# Radar_Analog.net
KiCad netlist of a schematic drawn in Altium Designer
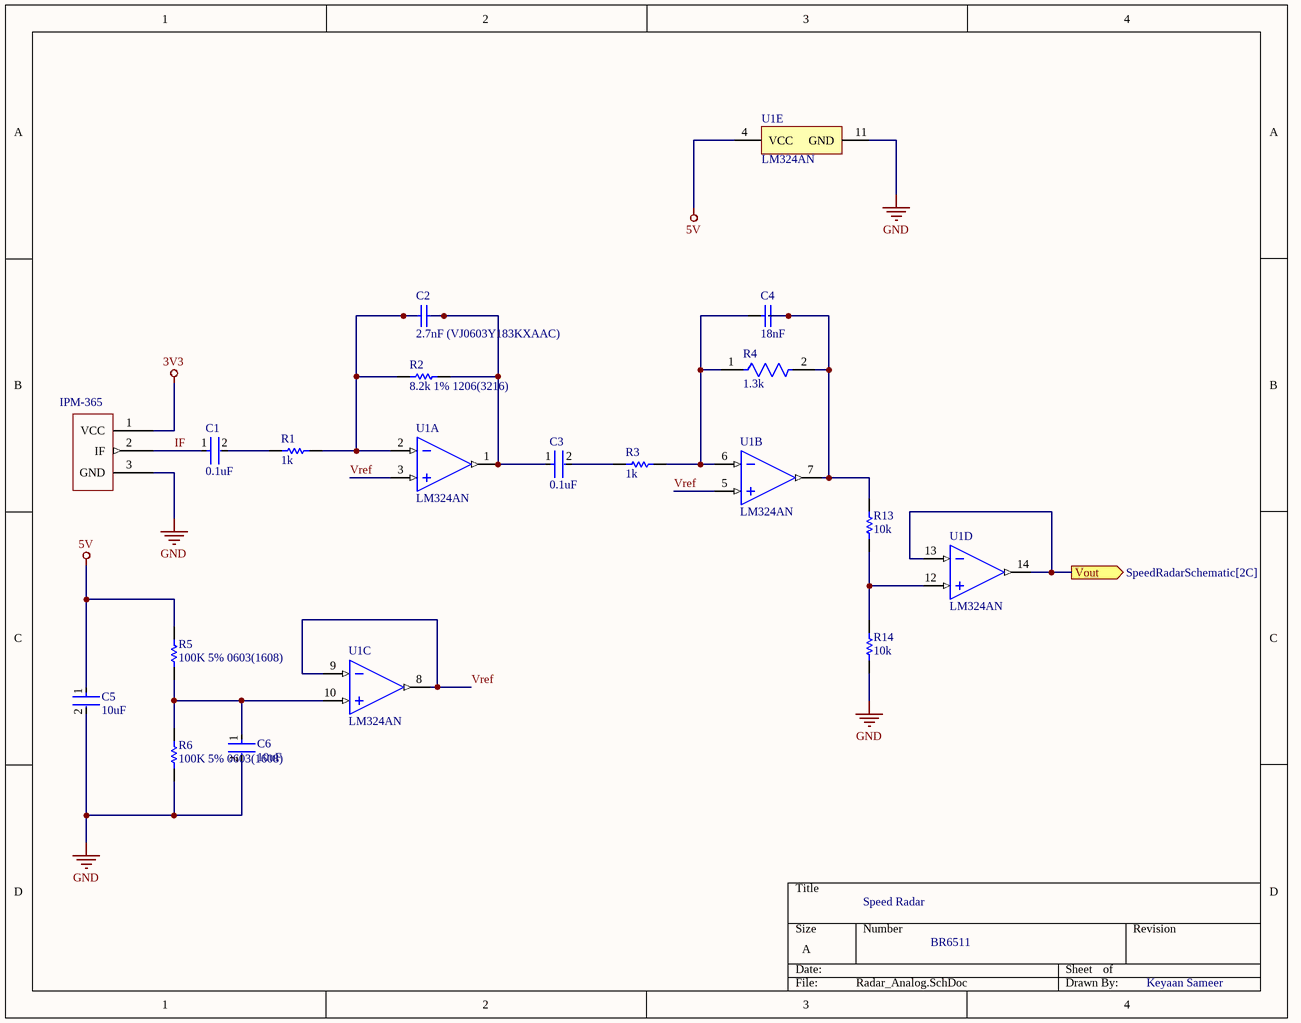
[diagram p0: Radar_Analog.SchDoc]

(export (version "E")
  (design (tool "Eeschema 10.0.6"))
  (components
    (comp (ref "C1")
      (value "0.1uF")
      (footprint "FP-GCD21B-0_15-IPC_A")
      (fields (field (name "Comment") "GCD21BR71H104KA01L"))
      (libsource (lib "Dallas Formula Racing EV - University of Texas at Dallas") (part "b4654b650e69147ec39a6b967a45e02"))
    )
    (comp (ref "C2")
      (value "2.7nF (VJ0603Y183KXAAC)")
      (footprint "CAPC1608X92X38ML15T08")
      (fields (field (name "MANUFACTURER") "Vitramon") (field (name "PART NUMBER") "VJ0603Y183KXAAC"))
      (libsource (lib "Altium Content Vault") (part "CAP"))
    )
    (comp (ref "C3")
      (value "0.1uF")
      (footprint "FP-GCD21B-0_15-IPC_A")
      (fields (field (name "Comment") "GCD21BR71H104KA01L"))
      (libsource (lib "Dallas Formula Racing EV - University of Texas at Dallas") (part "b4654b650e69147ec39a6b967a45e02"))
    )
    (comp (ref "C4")
      (value "18nF")
      (footprint "CAPC1608X92X38ML15T08")
      (fields (field (name "MANUFACTURER") "Vitramon") (field (name "PART NUMBER") "VJ0603Y183JXXAC"))
      (libsource (lib "Altium Content Vault") (part "CAP"))
    )
    (comp (ref "C5")
      (value "10uF")
      (footprint "FP-C0805C106K8RACAUTO-MFG")
      (description "CAP CER 10UF 10V X7R 0805")
      (fields (field (name "TOLERANCE") "10%"))
      (libsource (lib "Altium Content Vault") (part "b4654b650e69147ec39a6b967a45e02"))
    )
    (comp (ref "C6")
      (value "10uF")
      (footprint "FP-C0805C106K8RACAUTO-MFG")
      (description "CAP CER 10UF 10V X7R 0805")
      (fields (field (name "TOLERANCE") "10%"))
      (libsource (lib "Altium Content Vault") (part "b4654b650e69147ec39a6b967a45e02"))
    )
    (comp (ref "IPM-365")
      (value "Component_1")
      (footprint "PCBComponent_1")
      (libsource (lib "IPM-365") (part "Component_1"))
    )
    (comp (ref "R1")
      (value "1k")
      (footprint "RESC0805(2012)_L")
      (description "Chip Resistor, 1 kOhms, +/-5%, 125 mW, -55 to 155 degC, 0805")
      (fields (field (name "TOLERANCE") "5%") (field (name "POWER") "125mW"))
      (libsource (lib "Dallas Formula Racing EV - University of Texas at Dallas") (part "RES-2"))
    )
    (comp (ref "R2")
      (value "8.2k 1% 1206(3216)")
      (footprint "RESC1206(3216)_M")
      (description "8K2 0.25W 1% 1206 (3216 Metric)  SMD")
      (fields (field (name "TOLERANCE") "1 %") (field (name "POWER") "0.25 W"))
      (libsource (lib "Altium Content Vault") (part "RES"))
    )
    (comp (ref "R3")
      (value "1k")
      (footprint "RESC0805(2012)_L")
      (description "Chip Resistor, 1 kOhms, +/-5%, 125 mW, -55 to 155 degC, 0805")
      (fields (field (name "TOLERANCE") "5%") (field (name "POWER") "125mW"))
      (libsource (lib "Dallas Formula Racing EV - University of Texas at Dallas") (part "RES-2"))
    )
    (comp (ref "R4")
      (value "1.3k")
      (footprint "FP-TFCR0603-IPC_B")
      (description "RES Thin Film,  1.3kΩ, 0.1%, 0.1W, 25ppm/°C, 0603")
      (libsource (lib "Altium Content Vault") (part "1029c3af85768c4190bb7ad29bc67b5"))
    )
    (comp (ref "R5")
      (value "100K 5% 0603(1608)")
      (footprint "RESC0603(1608)_N")
      (description "100K 0.1W 5% 0603 (1608 Metric)  SMD")
      (fields (field (name "TOLERANCE") "5 %") (field (name "POWER") "0.1 W"))
      (libsource (lib "Altium Content Vault") (part "RES"))
    )
    (comp (ref "R6")
      (value "100K 5% 0603(1608)")
      (footprint "RESC0603(1608)_N")
      (description "100K 0.1W 5% 0603 (1608 Metric)  SMD")
      (fields (field (name "TOLERANCE") "5 %") (field (name "POWER") "0.1 W"))
      (libsource (lib "Altium Content Vault") (part "RES"))
    )
    (comp (ref "R13")
      (value "10k")
      (footprint "RESC2013X50X35ML15T15")
      (description "Chip Resistor, 10 KOhm, +/- 1%, 125 mW, -55 to 155 degC, 0805 (2012 Metric)")
      (fields (field (name "POWER") "125mW") (field (name "TOLERANCE") "1%"))
      (libsource (lib "Dallas Formula Racing EV - University of Texas at Dallas") (part "RES-2"))
    )
    (comp (ref "R14")
      (value "10k")
      (footprint "RESC2013X50X35ML15T15")
      (description "Chip Resistor, 10 KOhm, +/- 1%, 125 mW, -55 to 155 degC, 0805 (2012 Metric)")
      (fields (field (name "POWER") "125mW") (field (name "TOLERANCE") "1%"))
      (libsource (lib "Dallas Formula Racing EV - University of Texas at Dallas") (part "RES-2"))
    )
    (comp (ref "U1")
      (value "LM324AN")
      (footprint "TI-N0014A")
      (description "Quadruple Operational Amplifier, 1.2 MHz, 0 to 70 degC, 14-Pin PDIP (N), Pb-Free (RoHS), Tube")
      (fields (field (name "MANUFACTURER") "Texas Instruments (TI)"))
      (libsource (lib "Dallas Formula Racing EV - University of Texas at Dallas") (part "TI-LMX24-14"))
    )
  )
  (nets
    (net (code "1") (name "/IF") (class "Default")
      (node (ref "C1") (pin "1") (pinfunction "1_1") (pintype "passive"))
      (node (ref "IPM-365") (pin "2") (pinfunction "IF_2") (pintype "output"))
    )
    (net (code "2") (name "/Vout") (class "Default")
      (node (ref "U1") (pin "13") (pinfunction "4IN-_13") (pintype "input"))
      (node (ref "U1") (pin "14") (pinfunction "4OUT_14") (pintype "output"))
    )
    (net (code "3") (name "/Vref") (class "Default")
      (node (ref "U1") (pin "3") (pinfunction "1IN+_3") (pintype "input"))
      (node (ref "U1") (pin "5") (pinfunction "2IN+_5") (pintype "input"))
      (node (ref "U1") (pin "8") (pinfunction "3OUT_8") (pintype "output"))
      (node (ref "U1") (pin "9") (pinfunction "3IN-_9") (pintype "input"))
    )
    (net (code "4") (name "3V3") (class "Default")
      (node (ref "IPM-365") (pin "1") (pinfunction "VCC_1") (pintype "power_in"))
    )
    (net (code "5") (name "5V") (class "Default")
      (node (ref "C5") (pin "1") (pinfunction "1_1") (pintype "passive"))
      (node (ref "R5") (pin "2") (pinfunction "2_2") (pintype "passive"))
      (node (ref "U1") (pin "4") (pinfunction "VCC_4") (pintype "power_in"))
    )
    (net (code "6") (name "GND") (class "Default")
      (node (ref "C5") (pin "2") (pinfunction "2_2") (pintype "passive"))
      (node (ref "C6") (pin "2") (pinfunction "2_2") (pintype "passive"))
      (node (ref "IPM-365") (pin "3") (pinfunction "GND_3") (pintype "power_in"))
      (node (ref "R14") (pin "1") (pinfunction "1_1") (pintype "passive"))
      (node (ref "R6") (pin "1") (pinfunction "1_1") (pintype "passive"))
      (node (ref "U1") (pin "11") (pinfunction "GND_11") (pintype "power_in"))
    )
    (net (code "7") (name "Net-(C1-Pad2)") (class "Default")
      (node (ref "C1") (pin "2") (pinfunction "2_2") (pintype "passive"))
      (node (ref "R1") (pin "1") (pinfunction "1_1") (pintype "passive"))
    )
    (net (code "8") (name "Net-(C3-Pad2)") (class "Default")
      (node (ref "C3") (pin "2") (pinfunction "2_2") (pintype "passive"))
      (node (ref "R3") (pin "1") (pinfunction "1_1") (pintype "passive"))
    )
    (net (code "9") (name "Net-(U1A-1IN-)") (class "Default")
      (node (ref "C2") (pin "1") (pinfunction "1_1") (pintype "passive"))
      (node (ref "R1") (pin "2") (pinfunction "2_2") (pintype "passive"))
      (node (ref "R2") (pin "1") (pinfunction "1_1") (pintype "passive"))
      (node (ref "U1") (pin "2") (pinfunction "1IN-_2") (pintype "input"))
    )
    (net (code "10") (name "Net-(U1A-1OUT)") (class "Default")
      (node (ref "C2") (pin "2") (pinfunction "2_2") (pintype "passive"))
      (node (ref "C3") (pin "1") (pinfunction "1_1") (pintype "passive"))
      (node (ref "R2") (pin "2") (pinfunction "2_2") (pintype "passive"))
      (node (ref "U1") (pin "1") (pinfunction "1OUT_1") (pintype "output"))
    )
    (net (code "11") (name "Net-(U1B-2IN-)") (class "Default")
      (node (ref "C4") (pin "1") (pinfunction "1_1") (pintype "passive"))
      (node (ref "R3") (pin "2") (pinfunction "2_2") (pintype "passive"))
      (node (ref "R4") (pin "1") (pinfunction "1_1") (pintype "passive"))
      (node (ref "U1") (pin "6") (pinfunction "2IN-_6") (pintype "input"))
    )
    (net (code "12") (name "Net-(U1B-2OUT)") (class "Default")
      (node (ref "C4") (pin "2") (pinfunction "2_2") (pintype "passive"))
      (node (ref "R13") (pin "2") (pinfunction "2_2") (pintype "passive"))
      (node (ref "R4") (pin "2") (pinfunction "2_2") (pintype "passive"))
      (node (ref "U1") (pin "7") (pinfunction "2OUT_7") (pintype "output"))
    )
    (net (code "13") (name "Net-(U1C-3IN+)") (class "Default")
      (node (ref "C6") (pin "1") (pinfunction "1_1") (pintype "passive"))
      (node (ref "R5") (pin "1") (pinfunction "1_1") (pintype "passive"))
      (node (ref "R6") (pin "2") (pinfunction "2_2") (pintype "passive"))
      (node (ref "U1") (pin "10") (pinfunction "3IN+_10") (pintype "input"))
    )
    (net (code "14") (name "Net-(U1D-4IN+)") (class "Default")
      (node (ref "R13") (pin "1") (pinfunction "1_1") (pintype "passive"))
      (node (ref "R14") (pin "2") (pinfunction "2_2") (pintype "passive"))
      (node (ref "U1") (pin "12") (pinfunction "4IN+_12") (pintype "input"))
    )
  )
)
